# cff3100if.net
KiCad netlist of a schematic drawn in EAGLE
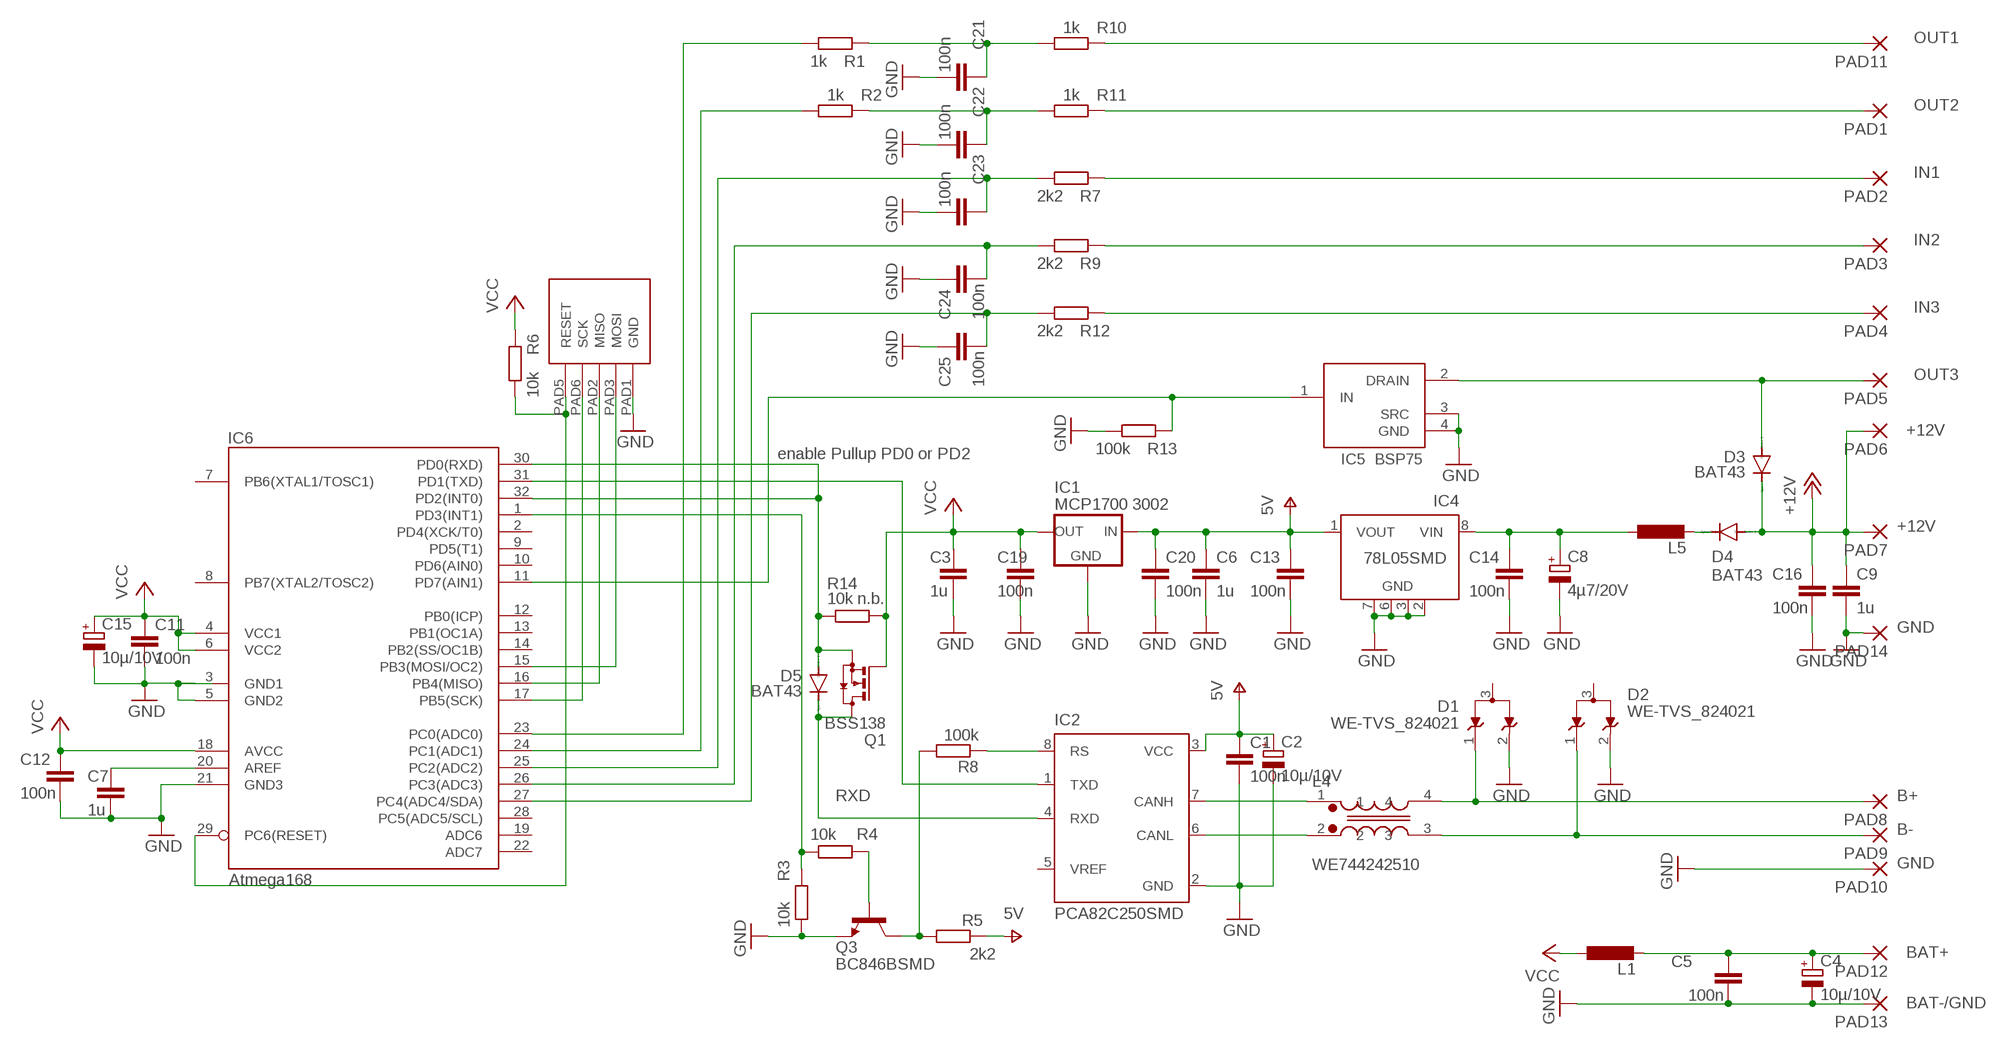
[diagram p0: schematic, sheet 1]

(export (version "E")
  (design (tool "Eeschema 10.0.6"))
  (components
    (comp (ref "C1")
      (value "100n")
      (footprint "eagle-import:C0603")
      (libsource (lib "eagle-import") (part "resistor_C-EUC0603"))
    )
    (comp (ref "C2")
      (value "10µ/10V")
      (footprint "eagle-import:A_3216-18W")
      (libsource (lib "eagle-import") (part "CPOL-EUA/3216-18W"))
    )
    (comp (ref "C3")
      (value "1u")
      (footprint "eagle-import:C1206")
      (libsource (lib "eagle-import") (part "C-EUC1206"))
    )
    (comp (ref "C4")
      (value "10µ/10V")
      (footprint "eagle-import:A_3216-18W")
      (libsource (lib "eagle-import") (part "CPOL-EUA/3216-18W"))
    )
    (comp (ref "C5")
      (value "100n")
      (footprint "eagle-import:C0603")
      (libsource (lib "eagle-import") (part "resistor_C-EUC0603"))
    )
    (comp (ref "C6")
      (value "1u")
      (footprint "eagle-import:C1206")
      (libsource (lib "eagle-import") (part "C-EUC1206"))
    )
    (comp (ref "C7")
      (value "1u")
      (footprint "eagle-import:C1206")
      (libsource (lib "eagle-import") (part "C-EUC1206"))
    )
    (comp (ref "C8")
      (value "4µ7/20V")
      (footprint "eagle-import:A_3216-18W")
      (libsource (lib "eagle-import") (part "CPOL-EUA/3216-18W"))
    )
    (comp (ref "C9")
      (value "1u")
      (footprint "eagle-import:C1206")
      (libsource (lib "eagle-import") (part "C-EUC1206"))
    )
    (comp (ref "C11")
      (value "100n")
      (footprint "eagle-import:C0603")
      (libsource (lib "eagle-import") (part "resistor_C-EUC0603"))
    )
    (comp (ref "C12")
      (value "100n")
      (footprint "eagle-import:C0603")
      (libsource (lib "eagle-import") (part "resistor_C-EUC0603"))
    )
    (comp (ref "C13")
      (value "100n")
      (footprint "eagle-import:C0603")
      (libsource (lib "eagle-import") (part "resistor_C-EUC0603"))
    )
    (comp (ref "C14")
      (value "100n")
      (footprint "eagle-import:C0603")
      (libsource (lib "eagle-import") (part "resistor_C-EUC0603"))
    )
    (comp (ref "C15")
      (value "10µ/10V")
      (footprint "eagle-import:A_3216-18W")
      (libsource (lib "eagle-import") (part "CPOL-EUA/3216-18W"))
    )
    (comp (ref "C16")
      (value "100n")
      (footprint "eagle-import:C0603")
      (libsource (lib "eagle-import") (part "resistor_C-EUC0603"))
    )
    (comp (ref "C19")
      (value "100n")
      (footprint "eagle-import:C0603")
      (libsource (lib "eagle-import") (part "resistor_C-EUC0603"))
    )
    (comp (ref "C20")
      (value "100n")
      (footprint "eagle-import:C0603")
      (libsource (lib "eagle-import") (part "resistor_C-EUC0603"))
    )
    (comp (ref "C21")
      (value "100n")
      (footprint "eagle-import:C0603")
      (libsource (lib "eagle-import") (part "resistor_C-EUC0603"))
    )
    (comp (ref "C22")
      (value "100n")
      (footprint "eagle-import:C0603")
      (libsource (lib "eagle-import") (part "resistor_C-EUC0603"))
    )
    (comp (ref "C23")
      (value "100n")
      (footprint "eagle-import:C0603")
      (libsource (lib "eagle-import") (part "resistor_C-EUC0603"))
    )
    (comp (ref "C24")
      (value "100n")
      (footprint "eagle-import:C0603")
      (libsource (lib "eagle-import") (part "resistor_C-EUC0603"))
    )
    (comp (ref "C25")
      (value "100n")
      (footprint "eagle-import:C0603")
      (libsource (lib "eagle-import") (part "resistor_C-EUC0603"))
    )
    (comp (ref "D1")
      (value "WE-TVS_824021")
      (footprint "eagle-import:WE-TVS_SOT23-3L")
      (libsource (lib "eagle-import") (part "WE-TVS_824021"))
    )
    (comp (ref "D2")
      (value "WE-TVS_824021")
      (footprint "eagle-import:WE-TVS_SOT23-3L")
      (libsource (lib "eagle-import") (part "WE-TVS_824021"))
    )
    (comp (ref "D3")
      (value "BAT43")
      (footprint "eagle-import:MINIMELF")
      (libsource (lib "eagle-import") (part "DIODE-MINIMELF"))
    )
    (comp (ref "D4")
      (value "BAT43")
      (footprint "eagle-import:MINIMELF")
      (libsource (lib "eagle-import") (part "DIODE-MINIMELF"))
    )
    (comp (ref "D5")
      (value "BAT43")
      (footprint "eagle-import:MINIMELF")
      (libsource (lib "eagle-import") (part "DIODE-MINIMELF"))
    )
    (comp (ref "IC1")
      (value "MCP1700 3002")
      (footprint "eagle-import:SOT23")
      (libsource (lib "eagle-import") (part "XC63FPM"))
    )
    (comp (ref "IC2")
      (value "PCA82C250SMD")
      (footprint "eagle-import:SO8")
      (libsource (lib "eagle-import") (part "PCA82C250SMD"))
    )
    (comp (ref "IC4")
      (value "78L05SMD")
      (footprint "eagle-import:SO08")
      (libsource (lib "eagle-import") (part "78LSMD05"))
    )
    (comp (ref "IC5")
      (value "BSP75")
      (footprint "eagle-import:SOT223")
      (libsource (lib "eagle-import") (part "BSP75"))
    )
    (comp (ref "IC6")
      (value "Atmega168")
      (footprint "eagle-import:TQFP32-08")
      (libsource (lib "eagle-import") (part "ATMEGA8"))
    )
    (comp (ref "L1")
      (value "L-EUL1806")
      (footprint "eagle-import:L1806")
      (libsource (lib "eagle-import") (part "L-EUL1806"))
    )
    (comp (ref "L4")
      (value "WE744242510")
      (footprint "eagle-import:WE-SLM")
      (libsource (lib "eagle-import") (part "WE-SLM"))
    )
    (comp (ref "L5")
      (value "L-EUL1806")
      (footprint "eagle-import:L1806")
      (libsource (lib "eagle-import") (part "L-EUL1806"))
    )
    (comp (ref "PAD1")
      (value "1,6/0,9")
      (footprint "eagle-import:1,6_0,9")
      (libsource (lib "eagle-import") (part "1,6/0,9"))
    )
    (comp (ref "PAD2")
      (value "1,6/0,9")
      (footprint "eagle-import:1,6_0,9")
      (libsource (lib "eagle-import") (part "1,6/0,9"))
    )
    (comp (ref "PAD3")
      (value "1,6/0,9")
      (footprint "eagle-import:1,6_0,9")
      (libsource (lib "eagle-import") (part "1,6/0,9"))
    )
    (comp (ref "PAD4")
      (value "1,6/0,9")
      (footprint "eagle-import:1,6_0,9")
      (libsource (lib "eagle-import") (part "1,6/0,9"))
    )
    (comp (ref "PAD5")
      (value "1,6/0,9")
      (footprint "eagle-import:1,6_0,9")
      (libsource (lib "eagle-import") (part "1,6/0,9"))
    )
    (comp (ref "PAD6")
      (value "+12V")
      (footprint "eagle-import:1,6_0,9")
      (libsource (lib "eagle-import") (part "1,6/0,9"))
    )
    (comp (ref "PAD7")
      (value "1,6/0,9")
      (footprint "eagle-import:1,6_0,9")
      (libsource (lib "eagle-import") (part "1,6/0,9"))
    )
    (comp (ref "PAD8")
      (value "1,6/0,9")
      (footprint "eagle-import:1,6_0,9")
      (libsource (lib "eagle-import") (part "1,6/0,9"))
    )
    (comp (ref "PAD9")
      (value "1,6/0,9")
      (footprint "eagle-import:1,6_0,9")
      (libsource (lib "eagle-import") (part "1,6/0,9"))
    )
    (comp (ref "PAD10")
      (value "1,6/0,9")
      (footprint "eagle-import:1,6_0,9")
      (libsource (lib "eagle-import") (part "1,6/0,9"))
    )
    (comp (ref "PAD11")
      (value "1,6/0,9")
      (footprint "eagle-import:1,6_0,9")
      (libsource (lib "eagle-import") (part "1,6/0,9"))
    )
    (comp (ref "PAD12")
      (value "BAT+")
      (footprint "eagle-import:1,6_0,9")
      (libsource (lib "eagle-import") (part "1,6/0,9"))
    )
    (comp (ref "PAD13")
      (value "BAT-/GND")
      (footprint "eagle-import:1,6_0,9")
      (libsource (lib "eagle-import") (part "1,6/0,9"))
    )
    (comp (ref "PAD14")
      (value "1,6/0,9")
      (footprint "eagle-import:1,6_0,9")
      (libsource (lib "eagle-import") (part "1,6/0,9"))
    )
    (comp (ref "Q1")
      (value "BSS138")
      (footprint "eagle-import:SOT23")
      (libsource (lib "eagle-import") (part "BSS123"))
    )
    (comp (ref "Q3")
      (value "BC846BSMD")
      (footprint "eagle-import:SOT23")
      (libsource (lib "eagle-import") (part "BC846SMDB"))
    )
    (comp (ref "R1")
      (value "1k")
      (footprint "eagle-import:R0603")
      (libsource (lib "eagle-import") (part "R-EU_R0603"))
    )
    (comp (ref "R2")
      (value "1k")
      (footprint "eagle-import:R0603")
      (libsource (lib "eagle-import") (part "R-EU_R0603"))
    )
    (comp (ref "R3")
      (value "10k")
      (footprint "eagle-import:R0603")
      (libsource (lib "eagle-import") (part "R-EU_R0603"))
    )
    (comp (ref "R4")
      (value "10k")
      (footprint "eagle-import:R0603")
      (libsource (lib "eagle-import") (part "R-EU_R0603"))
    )
    (comp (ref "R5")
      (value "2k2")
      (footprint "eagle-import:R0603")
      (libsource (lib "eagle-import") (part "R-EU_R0603"))
    )
    (comp (ref "R6")
      (value "10k")
      (footprint "eagle-import:R0603")
      (libsource (lib "eagle-import") (part "R-EU_R0603"))
    )
    (comp (ref "R7")
      (value "2k2")
      (footprint "eagle-import:R0603")
      (libsource (lib "eagle-import") (part "R-EU_R0603"))
    )
    (comp (ref "R8")
      (value "100k")
      (footprint "eagle-import:R0603")
      (libsource (lib "eagle-import") (part "resistor_R-EU_R0603"))
    )
    (comp (ref "R9")
      (value "2k2")
      (footprint "eagle-import:R0603")
      (libsource (lib "eagle-import") (part "R-EU_R0603"))
    )
    (comp (ref "R10")
      (value "1k")
      (footprint "eagle-import:R0603")
      (libsource (lib "eagle-import") (part "R-EU_R0603"))
    )
    (comp (ref "R11")
      (value "1k")
      (footprint "eagle-import:R0603")
      (libsource (lib "eagle-import") (part "R-EU_R0603"))
    )
    (comp (ref "R12")
      (value "2k2")
      (footprint "eagle-import:R0603")
      (libsource (lib "eagle-import") (part "R-EU_R0603"))
    )
    (comp (ref "R13")
      (value "100k")
      (footprint "eagle-import:R0603")
      (libsource (lib "eagle-import") (part "R-EU_R0603"))
    )
    (comp (ref "R14")
      (value "10k n.b.")
      (footprint "eagle-import:R0603")
      (libsource (lib "eagle-import") (part "R-EU_R0603"))
    )
    (comp (ref "U$2")
      (value "ATMEL_ISP")
      (footprint "eagle-import:ATMEL_ISP")
      (libsource (lib "eagle-import") (part "ATMEL_ISP"))
    )
  )
  (nets
    (net (code "1") (name "+12V") (class "Default")
      (node (ref "C16") (pin "1") (pinfunction "1_1") (pintype "passive"))
      (node (ref "C9") (pin "1") (pinfunction "1_1") (pintype "passive"))
      (node (ref "D3") (pin "C") (pinfunction "C_C") (pintype "passive"))
      (node (ref "D4") (pin "A") (pinfunction "A_A") (pintype "passive"))
      (node (ref "PAD6") (pin "1") (pinfunction "P_1") (pintype "passive"))
      (node (ref "PAD7") (pin "1") (pinfunction "P_1") (pintype "passive"))
    )
    (net (code "2") (name "/B+") (class "Default")
      (node (ref "D1") (pin "1") (pinfunction "1_1") (pintype "passive"))
      (node (ref "L4") (pin "4") (pinfunction "4_4") (pintype "bidirectional"))
      (node (ref "PAD8") (pin "1") (pinfunction "P_1") (pintype "passive"))
    )
    (net (code "3") (name "/B-") (class "Default")
      (node (ref "D2") (pin "1") (pinfunction "1_1") (pintype "passive"))
      (node (ref "L4") (pin "3") (pinfunction "3_3") (pintype "bidirectional"))
      (node (ref "PAD9") (pin "1") (pinfunction "P_1") (pintype "passive"))
    )
    (net (code "4") (name "/IN1") (class "Default")
      (node (ref "PAD2") (pin "1") (pinfunction "P_1") (pintype "passive"))
      (node (ref "R7") (pin "1") (pinfunction "1_1") (pintype "passive"))
    )
    (net (code "5") (name "/IN2") (class "Default")
      (node (ref "PAD3") (pin "1") (pinfunction "P_1") (pintype "passive"))
      (node (ref "R9") (pin "1") (pinfunction "1_1") (pintype "passive"))
    )
    (net (code "6") (name "/IN3") (class "Default")
      (node (ref "PAD4") (pin "1") (pinfunction "P_1") (pintype "passive"))
      (node (ref "R12") (pin "1") (pinfunction "1_1") (pintype "passive"))
    )
    (net (code "7") (name "/OUT1") (class "Default")
      (node (ref "PAD11") (pin "1") (pinfunction "P_1") (pintype "passive"))
      (node (ref "R10") (pin "1") (pinfunction "1_1") (pintype "passive"))
    )
    (net (code "8") (name "/OUT2") (class "Default")
      (node (ref "PAD1") (pin "1") (pinfunction "P_1") (pintype "passive"))
      (node (ref "R11") (pin "1") (pinfunction "1_1") (pintype "passive"))
    )
    (net (code "9") (name "/OUT3") (class "Default")
      (node (ref "D3") (pin "A") (pinfunction "A_A") (pintype "passive"))
      (node (ref "IC5") (pin "2") (pinfunction "DRAIN_2") (pintype "output"))
      (node (ref "PAD5") (pin "1") (pinfunction "P_1") (pintype "passive"))
    )
    (net (code "10") (name "/RXD") (class "Default")
      (node (ref "D5") (pin "C") (pinfunction "C_C") (pintype "passive"))
      (node (ref "IC2") (pin "4") (pinfunction "RXD_4") (pintype "output"))
      (node (ref "Q1") (pin "3") (pinfunction "D_3") (pintype "passive"))
    )
    (net (code "11") (name "5V") (class "Default")
      (node (ref "C1") (pin "1") (pinfunction "1_1") (pintype "passive"))
      (node (ref "C13") (pin "1") (pinfunction "1_1") (pintype "passive"))
      (node (ref "C2") (pin "+") (pinfunction "+_+") (pintype "passive"))
      (node (ref "C20") (pin "1") (pinfunction "1_1") (pintype "passive"))
      (node (ref "C6") (pin "1") (pinfunction "1_1") (pintype "passive"))
      (node (ref "IC1") (pin "3") (pinfunction "IN_3") (pintype "input"))
      (node (ref "IC2") (pin "3") (pinfunction "VCC_3") (pintype "power_in"))
      (node (ref "IC4") (pin "1") (pinfunction "VOUT_1") (pintype "output"))
      (node (ref "R5") (pin "2") (pinfunction "2_2") (pintype "passive"))
    )
    (net (code "12") (name "GND") (class "Default")
      (node (ref "C1") (pin "2") (pinfunction "2_2") (pintype "passive"))
      (node (ref "C11") (pin "2") (pinfunction "2_2") (pintype "passive"))
      (node (ref "C12") (pin "2") (pinfunction "2_2") (pintype "passive"))
      (node (ref "C13") (pin "2") (pinfunction "2_2") (pintype "passive"))
      (node (ref "C14") (pin "2") (pinfunction "2_2") (pintype "passive"))
      (node (ref "C15") (pin "-") (pinfunction "-_-") (pintype "passive"))
      (node (ref "C16") (pin "2") (pinfunction "2_2") (pintype "passive"))
      (node (ref "C19") (pin "2") (pinfunction "2_2") (pintype "passive"))
      (node (ref "C2") (pin "-") (pinfunction "-_-") (pintype "passive"))
      (node (ref "C20") (pin "2") (pinfunction "2_2") (pintype "passive"))
      (node (ref "C21") (pin "2") (pinfunction "2_2") (pintype "passive"))
      (node (ref "C22") (pin "2") (pinfunction "2_2") (pintype "passive"))
      (node (ref "C23") (pin "2") (pinfunction "2_2") (pintype "passive"))
      (node (ref "C24") (pin "1") (pinfunction "1_1") (pintype "passive"))
      (node (ref "C25") (pin "1") (pinfunction "1_1") (pintype "passive"))
      (node (ref "C3") (pin "2") (pinfunction "2_2") (pintype "passive"))
      (node (ref "C4") (pin "-") (pinfunction "-_-") (pintype "passive"))
      (node (ref "C5") (pin "2") (pinfunction "2_2") (pintype "passive"))
      (node (ref "C6") (pin "2") (pinfunction "2_2") (pintype "passive"))
      (node (ref "C7") (pin "2") (pinfunction "2_2") (pintype "passive"))
      (node (ref "C8") (pin "-") (pinfunction "-_-") (pintype "passive"))
      (node (ref "C9") (pin "2") (pinfunction "2_2") (pintype "passive"))
      (node (ref "D1") (pin "2") (pinfunction "2_2") (pintype "passive"))
      (node (ref "D2") (pin "2") (pinfunction "2_2") (pintype "passive"))
      (node (ref "IC1") (pin "1") (pinfunction "GND_1") (pintype "input"))
      (node (ref "IC2") (pin "2") (pinfunction "GND_2") (pintype "power_in"))
      (node (ref "IC4") (pin "2") (pinfunction "GND_2") (pintype "power_in"))
      (node (ref "IC4") (pin "3") (pinfunction "GND_3") (pintype "power_in"))
      (node (ref "IC4") (pin "6") (pinfunction "GND_6") (pintype "power_in"))
      (node (ref "IC4") (pin "7") (pinfunction "GND_7") (pintype "power_in"))
      (node (ref "IC5") (pin "3") (pinfunction "SRC_3") (pintype "power_in"))
      (node (ref "IC5") (pin "4") (pinfunction "GND_4") (pintype "power_in"))
      (node (ref "IC6") (pin "21") (pinfunction "GND3_21") (pintype "power_in"))
      (node (ref "IC6") (pin "3") (pinfunction "GND1_3") (pintype "power_in"))
      (node (ref "IC6") (pin "5") (pinfunction "GND2_5") (pintype "power_in"))
      (node (ref "PAD10") (pin "1") (pinfunction "P_1") (pintype "passive"))
      (node (ref "PAD13") (pin "1") (pinfunction "P_1") (pintype "passive"))
      (node (ref "PAD14") (pin "1") (pinfunction "P_1") (pintype "passive"))
      (node (ref "Q3") (pin "2") (pinfunction "E_2") (pintype "passive"))
      (node (ref "R13") (pin "2") (pinfunction "2_2") (pintype "passive"))
      (node (ref "R3") (pin "2") (pinfunction "2_2") (pintype "passive"))
      (node (ref "U$2") (pin "PAD1") (pinfunction "GND_PAD1") (pintype "power_in"))
    )
    (net (code "13") (name "Net-(C21-Pad1)") (class "Default")
      (node (ref "C21") (pin "1") (pinfunction "1_1") (pintype "passive"))
      (node (ref "R1") (pin "1") (pinfunction "1_1") (pintype "passive"))
      (node (ref "R10") (pin "2") (pinfunction "2_2") (pintype "passive"))
    )
    (net (code "14") (name "Net-(C22-Pad1)") (class "Default")
      (node (ref "C22") (pin "1") (pinfunction "1_1") (pintype "passive"))
      (node (ref "R11") (pin "2") (pinfunction "2_2") (pintype "passive"))
      (node (ref "R2") (pin "1") (pinfunction "1_1") (pintype "passive"))
    )
    (net (code "15") (name "Net-(D4-PadC)") (class "Default")
      (node (ref "D4") (pin "C") (pinfunction "C_C") (pintype "passive"))
      (node (ref "L5") (pin "2") (pinfunction "2_2") (pintype "passive"))
    )
    (net (code "16") (name "Net-(IC2-CANH)") (class "Default")
      (node (ref "IC2") (pin "7") (pinfunction "CANH_7") (pintype "bidirectional"))
      (node (ref "L4") (pin "1") (pinfunction "1_1") (pintype "bidirectional"))
    )
    (net (code "17") (name "Net-(IC2-CANL)") (class "Default")
      (node (ref "IC2") (pin "6") (pinfunction "CANL_6") (pintype "bidirectional"))
      (node (ref "L4") (pin "2") (pinfunction "2_2") (pintype "bidirectional"))
    )
    (net (code "18") (name "Net-(IC2-RS)") (class "Default")
      (node (ref "IC2") (pin "8") (pinfunction "RS_8") (pintype "input"))
      (node (ref "R8") (pin "1") (pinfunction "1_1") (pintype "passive"))
    )
    (net (code "19") (name "Net-(IC2-TXD)") (class "Default")
      (node (ref "IC2") (pin "1") (pinfunction "TXD_1") (pintype "input"))
      (node (ref "IC6") (pin "31") (pinfunction "PD1(TXD)_31") (pintype "bidirectional"))
    )
    (net (code "20") (name "Net-(IC4A-VIN)") (class "Default")
      (node (ref "C14") (pin "1") (pinfunction "1_1") (pintype "passive"))
      (node (ref "C8") (pin "+") (pinfunction "+_+") (pintype "passive"))
      (node (ref "IC4") (pin "8") (pinfunction "VIN_8") (pintype "passive"))
      (node (ref "L5") (pin "1") (pinfunction "1_1") (pintype "passive"))
    )
    (net (code "21") (name "Net-(IC5-IN)") (class "Default")
      (node (ref "IC5") (pin "1") (pinfunction "IN_1") (pintype "input"))
      (node (ref "IC6") (pin "11") (pinfunction "PD7(AIN1)_11") (pintype "bidirectional"))
      (node (ref "R13") (pin "1") (pinfunction "1_1") (pintype "passive"))
    )
    (net (code "22") (name "Net-(IC6-AREF)") (class "Default")
      (node (ref "C7") (pin "1") (pinfunction "1_1") (pintype "passive"))
      (node (ref "IC6") (pin "20") (pinfunction "AREF_20") (pintype "power_in"))
    )
    (net (code "23") (name "Net-(IC6-PB3(MOSI{slash}OC2))") (class "Default")
      (node (ref "IC6") (pin "15") (pinfunction "PB3(MOSI/OC2)_15") (pintype "bidirectional"))
      (node (ref "U$2") (pin "PAD3") (pinfunction "MOSI_PAD3") (pintype "bidirectional"))
    )
    (net (code "24") (name "Net-(IC6-PB4(MISO))") (class "Default")
      (node (ref "IC6") (pin "16") (pinfunction "PB4(MISO)_16") (pintype "bidirectional"))
      (node (ref "U$2") (pin "PAD2") (pinfunction "MISO_PAD2") (pintype "bidirectional"))
    )
    (net (code "25") (name "Net-(IC6-PB5(SCK))") (class "Default")
      (node (ref "IC6") (pin "17") (pinfunction "PB5(SCK)_17") (pintype "bidirectional"))
      (node (ref "U$2") (pin "PAD6") (pinfunction "SCK_PAD6") (pintype "bidirectional"))
    )
    (net (code "26") (name "Net-(IC6-PC0(ADC0))") (class "Default")
      (node (ref "IC6") (pin "23") (pinfunction "PC0(ADC0)_23") (pintype "bidirectional"))
      (node (ref "R1") (pin "2") (pinfunction "2_2") (pintype "passive"))
    )
    (net (code "27") (name "Net-(IC6-PC1(ADC1))") (class "Default")
      (node (ref "IC6") (pin "24") (pinfunction "PC1(ADC1)_24") (pintype "bidirectional"))
      (node (ref "R2") (pin "2") (pinfunction "2_2") (pintype "passive"))
    )
    (net (code "28") (name "Net-(IC6-PC2(ADC2))") (class "Default")
      (node (ref "C23") (pin "1") (pinfunction "1_1") (pintype "passive"))
      (node (ref "IC6") (pin "25") (pinfunction "PC2(ADC2)_25") (pintype "bidirectional"))
      (node (ref "R7") (pin "2") (pinfunction "2_2") (pintype "passive"))
    )
    (net (code "29") (name "Net-(IC6-PC3(ADC3))") (class "Default")
      (node (ref "C24") (pin "2") (pinfunction "2_2") (pintype "passive"))
      (node (ref "IC6") (pin "26") (pinfunction "PC3(ADC3)_26") (pintype "bidirectional"))
      (node (ref "R9") (pin "2") (pinfunction "2_2") (pintype "passive"))
    )
    (net (code "30") (name "Net-(IC6-PC4(ADC4{slash}SDA))") (class "Default")
      (node (ref "C25") (pin "2") (pinfunction "2_2") (pintype "passive"))
      (node (ref "IC6") (pin "27") (pinfunction "PC4(ADC4/SDA)_27") (pintype "bidirectional"))
      (node (ref "R12") (pin "2") (pinfunction "2_2") (pintype "passive"))
    )
    (net (code "31") (name "Net-(IC6-PC6(RESET))") (class "Default")
      (node (ref "IC6") (pin "29") (pinfunction "PC6(RESET)_29") (pintype "bidirectional"))
      (node (ref "R6") (pin "2") (pinfunction "2_2") (pintype "passive"))
      (node (ref "U$2") (pin "PAD5") (pinfunction "RESET_PAD5") (pintype "bidirectional"))
    )
    (net (code "32") (name "Net-(IC6-PD0(RXD))") (class "Default")
      (node (ref "D5") (pin "A") (pinfunction "A_A") (pintype "passive"))
      (node (ref "IC6") (pin "30") (pinfunction "PD0(RXD)_30") (pintype "bidirectional"))
      (node (ref "IC6") (pin "32") (pinfunction "PD2(INT0)_32") (pintype "bidirectional"))
      (node (ref "Q1") (pin "2") (pinfunction "S_2") (pintype "passive"))
      (node (ref "R14") (pin "2") (pinfunction "2_2") (pintype "passive"))
    )
    (net (code "33") (name "Net-(IC6-PD3(INT1))") (class "Default")
      (node (ref "IC6") (pin "1") (pinfunction "PD3(INT1)_1") (pintype "bidirectional"))
      (node (ref "R3") (pin "1") (pinfunction "1_1") (pintype "passive"))
      (node (ref "R4") (pin "2") (pinfunction "2_2") (pintype "passive"))
    )
    (net (code "34") (name "Net-(PAD12-P)") (class "Default")
      (node (ref "C4") (pin "+") (pinfunction "+_+") (pintype "passive"))
      (node (ref "C5") (pin "1") (pinfunction "1_1") (pintype "passive"))
      (node (ref "L1") (pin "2") (pinfunction "2_2") (pintype "passive"))
      (node (ref "PAD12") (pin "1") (pinfunction "P_1") (pintype "passive"))
    )
    (net (code "35") (name "Net-(Q3-B)") (class "Default")
      (node (ref "Q3") (pin "1") (pinfunction "B_1") (pintype "passive"))
      (node (ref "R4") (pin "1") (pinfunction "1_1") (pintype "passive"))
    )
    (net (code "36") (name "Net-(Q3-C)") (class "Default")
      (node (ref "Q3") (pin "3") (pinfunction "C_3") (pintype "passive"))
      (node (ref "R5") (pin "1") (pinfunction "1_1") (pintype "passive"))
      (node (ref "R8") (pin "2") (pinfunction "2_2") (pintype "passive"))
    )
    (net (code "37") (name "VCC") (class "Default")
      (node (ref "C11") (pin "1") (pinfunction "1_1") (pintype "passive"))
      (node (ref "C12") (pin "1") (pinfunction "1_1") (pintype "passive"))
      (node (ref "C15") (pin "+") (pinfunction "+_+") (pintype "passive"))
      (node (ref "C19") (pin "1") (pinfunction "1_1") (pintype "passive"))
      (node (ref "C3") (pin "1") (pinfunction "1_1") (pintype "passive"))
      (node (ref "IC1") (pin "2") (pinfunction "OUT_2") (pintype "passive"))
      (node (ref "IC6") (pin "18") (pinfunction "AVCC_18") (pintype "power_in"))
      (node (ref "IC6") (pin "4") (pinfunction "VCC1_4") (pintype "power_in"))
      (node (ref "IC6") (pin "6") (pinfunction "VCC2_6") (pintype "power_in"))
      (node (ref "L1") (pin "1") (pinfunction "1_1") (pintype "passive"))
      (node (ref "Q1") (pin "1") (pinfunction "G_1") (pintype "passive"))
      (node (ref "R14") (pin "1") (pinfunction "1_1") (pintype "passive"))
      (node (ref "R6") (pin "1") (pinfunction "1_1") (pintype "passive"))
    )
    (net (code "38") (name "unconnected-(D1-GND-Pad3)") (class "Default")
      (node (ref "D1") (pin "3") (pinfunction "GND_3") (pintype "passive"))
    )
    (net (code "39") (name "unconnected-(D2-GND-Pad3)") (class "Default")
      (node (ref "D2") (pin "3") (pinfunction "GND_3") (pintype "passive"))
    )
    (net (code "40") (name "unconnected-(IC2-VREF-Pad5)") (class "Default")
      (node (ref "IC2") (pin "5") (pinfunction "VREF_5") (pintype "output"))
    )
    (net (code "41") (name "unconnected-(IC6-ADC6-Pad19)") (class "Default")
      (node (ref "IC6") (pin "19") (pinfunction "ADC6_19") (pintype "bidirectional"))
    )
    (net (code "42") (name "unconnected-(IC6-ADC7-Pad22)") (class "Default")
      (node (ref "IC6") (pin "22") (pinfunction "ADC7_22") (pintype "bidirectional"))
    )
    (net (code "43") (name "unconnected-(IC6-PB0(ICP)-Pad12)") (class "Default")
      (node (ref "IC6") (pin "12") (pinfunction "PB0(ICP)_12") (pintype "bidirectional"))
    )
    (net (code "44") (name "unconnected-(IC6-PB1(OC1A)-Pad13)") (class "Default")
      (node (ref "IC6") (pin "13") (pinfunction "PB1(OC1A)_13") (pintype "bidirectional"))
    )
    (net (code "45") (name "unconnected-(IC6-PB2(SS{slash}OC1B)-Pad14)") (class "Default")
      (node (ref "IC6") (pin "14") (pinfunction "PB2(SS/OC1B)_14") (pintype "bidirectional"))
    )
    (net (code "46") (name "unconnected-(IC6-PB6(XTAL1{slash}TOSC1)-Pad7)") (class "Default")
      (node (ref "IC6") (pin "7") (pinfunction "PB6(XTAL1/TOSC1)_7") (pintype "bidirectional"))
    )
    (net (code "47") (name "unconnected-(IC6-PB7(XTAL2{slash}TOSC2)-Pad8)") (class "Default")
      (node (ref "IC6") (pin "8") (pinfunction "PB7(XTAL2/TOSC2)_8") (pintype "bidirectional"))
    )
    (net (code "48") (name "unconnected-(IC6-PC5(ADC5{slash}SCL)-Pad28)") (class "Default")
      (node (ref "IC6") (pin "28") (pinfunction "PC5(ADC5/SCL)_28") (pintype "bidirectional"))
    )
    (net (code "49") (name "unconnected-(IC6-PD4(XCK{slash}T0)-Pad2)") (class "Default")
      (node (ref "IC6") (pin "2") (pinfunction "PD4(XCK/T0)_2") (pintype "bidirectional"))
    )
    (net (code "50") (name "unconnected-(IC6-PD5(T1)-Pad9)") (class "Default")
      (node (ref "IC6") (pin "9") (pinfunction "PD5(T1)_9") (pintype "bidirectional"))
    )
    (net (code "51") (name "unconnected-(IC6-PD6(AIN0)-Pad10)") (class "Default")
      (node (ref "IC6") (pin "10") (pinfunction "PD6(AIN0)_10") (pintype "bidirectional"))
    )
  )
)
